# Thermocouple_Amplifier_K.net
KiCad netlist of a schematic drawn in EAGLE
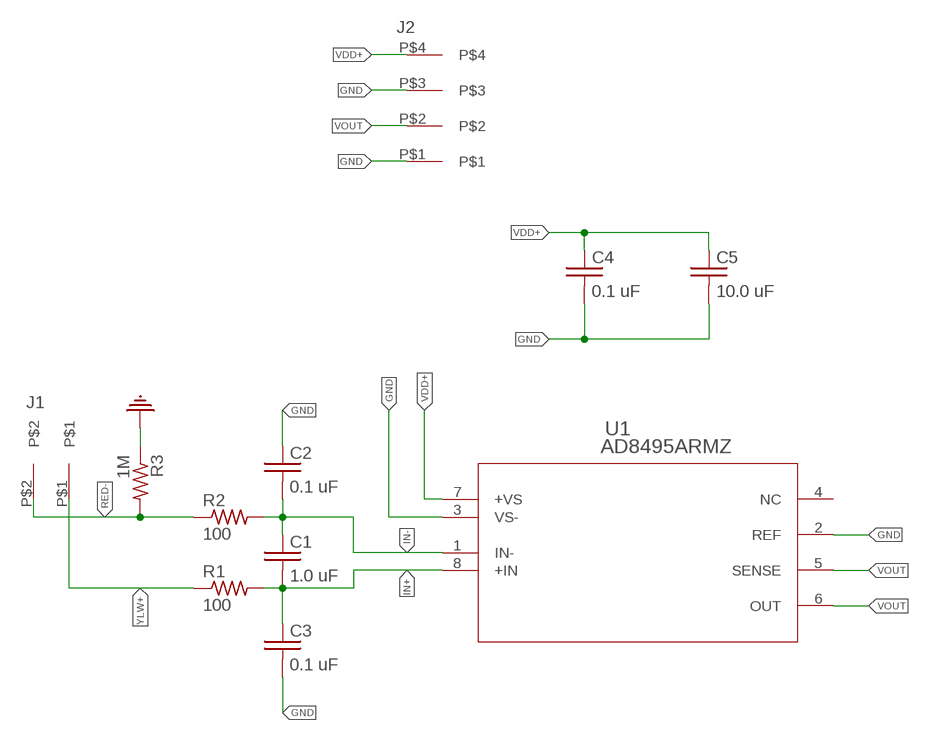
[diagram p0: schematic, sheet 1]

(export (version "E")
  (design (tool "Eeschema 10.0.6"))
  (components
    (comp (ref "C1")
      (value "1.0 uF")
      (footprint "eagle-import:0402")
      (libsource (lib "eagle-import") (part "C_0402"))
    )
    (comp (ref "C2")
      (value "0.1 uF")
      (footprint "eagle-import:0402")
      (libsource (lib "eagle-import") (part "C_0402"))
    )
    (comp (ref "C3")
      (value "0.1 uF")
      (footprint "eagle-import:0402")
      (libsource (lib "eagle-import") (part "C_0402"))
    )
    (comp (ref "C4")
      (value "0.1 uF")
      (footprint "eagle-import:0402")
      (libsource (lib "eagle-import") (part "C_0402"))
    )
    (comp (ref "C5")
      (value "10.0 uF")
      (footprint "eagle-import:0402")
      (libsource (lib "eagle-import") (part "C_0402"))
    )
    (comp (ref "J1")
      (value "3.81MM_1_X_2_RT_ANGLE_PLUG_HEADER")
      (footprint "eagle-import:2_3.81MM_PITCH")
      (libsource (lib "eagle-import") (part "3.81MM_1_X_2_RT_ANGLE_PLUG_HEADER"))
    )
    (comp (ref "J2")
      (value "3.81MM_1_X_4_RT_ANGLE_PLUG_HEADER")
      (footprint "eagle-import:1X4_3.81MM_PITCH")
      (libsource (lib "eagle-import") (part "3.81MM_1_X_4_RT_ANGLE_PLUG_HEADER"))
    )
    (comp (ref "R1")
      (value "100")
      (footprint "eagle-import:0402")
      (libsource (lib "eagle-import") (part "R_0402"))
    )
    (comp (ref "R2")
      (value "100")
      (footprint "eagle-import:0402")
      (libsource (lib "eagle-import") (part "R_0402"))
    )
    (comp (ref "R3")
      (value "1M")
      (footprint "eagle-import:0402")
      (libsource (lib "eagle-import") (part "R_0402"))
    )
    (comp (ref "U1")
      (value "AD8495ARMZ")
      (footprint "eagle-import:RM_8_ADI")
      (libsource (lib "eagle-import") (part "AD8495ARMZ"))
    )
  )
  (nets
    (net (code "1") (name "GND") (class "Default")
      (node (ref "C2") (pin "P$1") (pinfunction "1_P$1") (pintype "passive"))
      (node (ref "C3") (pin "P$2") (pinfunction "2_P$2") (pintype "passive"))
      (node (ref "C4") (pin "P$2") (pinfunction "2_P$2") (pintype "passive"))
      (node (ref "C5") (pin "P$2") (pinfunction "2_P$2") (pintype "passive"))
      (node (ref "J2") (pin "P$1") (pinfunction "P$1_P$1") (pintype "bidirectional"))
      (node (ref "J2") (pin "P$3") (pinfunction "P$3_P$3") (pintype "bidirectional"))
      (node (ref "R3") (pin "P$1") (pinfunction "1_P$1") (pintype "passive"))
      (node (ref "U1") (pin "2") (pinfunction "REF_2") (pintype "passive"))
      (node (ref "U1") (pin "3") (pinfunction "VS-_3") (pintype "power_in"))
    )
    (net (code "2") (name "IN+") (class "Default")
      (node (ref "C1") (pin "P$2") (pinfunction "2_P$2") (pintype "passive"))
      (node (ref "C3") (pin "P$1") (pinfunction "1_P$1") (pintype "passive"))
      (node (ref "R1") (pin "P$2") (pinfunction "2_P$2") (pintype "passive"))
      (node (ref "U1") (pin "8") (pinfunction "+IN_8") (pintype "input"))
    )
    (net (code "3") (name "IN-") (class "Default")
      (node (ref "C1") (pin "P$1") (pinfunction "1_P$1") (pintype "passive"))
      (node (ref "C2") (pin "P$2") (pinfunction "2_P$2") (pintype "passive"))
      (node (ref "R2") (pin "P$2") (pinfunction "2_P$2") (pintype "passive"))
      (node (ref "U1") (pin "1") (pinfunction "IN-_1") (pintype "input"))
    )
    (net (code "4") (name "RED-") (class "Default")
      (node (ref "J1") (pin "P$2") (pinfunction "P$2_P$2") (pintype "bidirectional"))
      (node (ref "R2") (pin "P$1") (pinfunction "1_P$1") (pintype "passive"))
      (node (ref "R3") (pin "P$2") (pinfunction "2_P$2") (pintype "passive"))
    )
    (net (code "5") (name "VDD+") (class "Default")
      (node (ref "C4") (pin "P$1") (pinfunction "1_P$1") (pintype "passive"))
      (node (ref "C5") (pin "P$1") (pinfunction "1_P$1") (pintype "passive"))
      (node (ref "J2") (pin "P$4") (pinfunction "P$4_P$4") (pintype "bidirectional"))
      (node (ref "U1") (pin "7") (pinfunction "+VS_7") (pintype "power_in"))
    )
    (net (code "6") (name "VOUT") (class "Default")
      (node (ref "J2") (pin "P$2") (pinfunction "P$2_P$2") (pintype "bidirectional"))
      (node (ref "U1") (pin "5") (pinfunction "SENSE_5") (pintype "passive"))
      (node (ref "U1") (pin "6") (pinfunction "OUT_6") (pintype "output"))
    )
    (net (code "7") (name "YLW+") (class "Default")
      (node (ref "J1") (pin "P$1") (pinfunction "P$1_P$1") (pintype "bidirectional"))
      (node (ref "R1") (pin "P$1") (pinfunction "1_P$1") (pintype "passive"))
    )
    (net (code "8") (name "unconnected-(U1-NC-Pad4)") (class "Default")
      (node (ref "U1") (pin "4") (pinfunction "NC_4") (pintype "no_connect"))
    )
  )
)
